# Driver.net
KiCad netlist of a schematic drawn in EAGLE
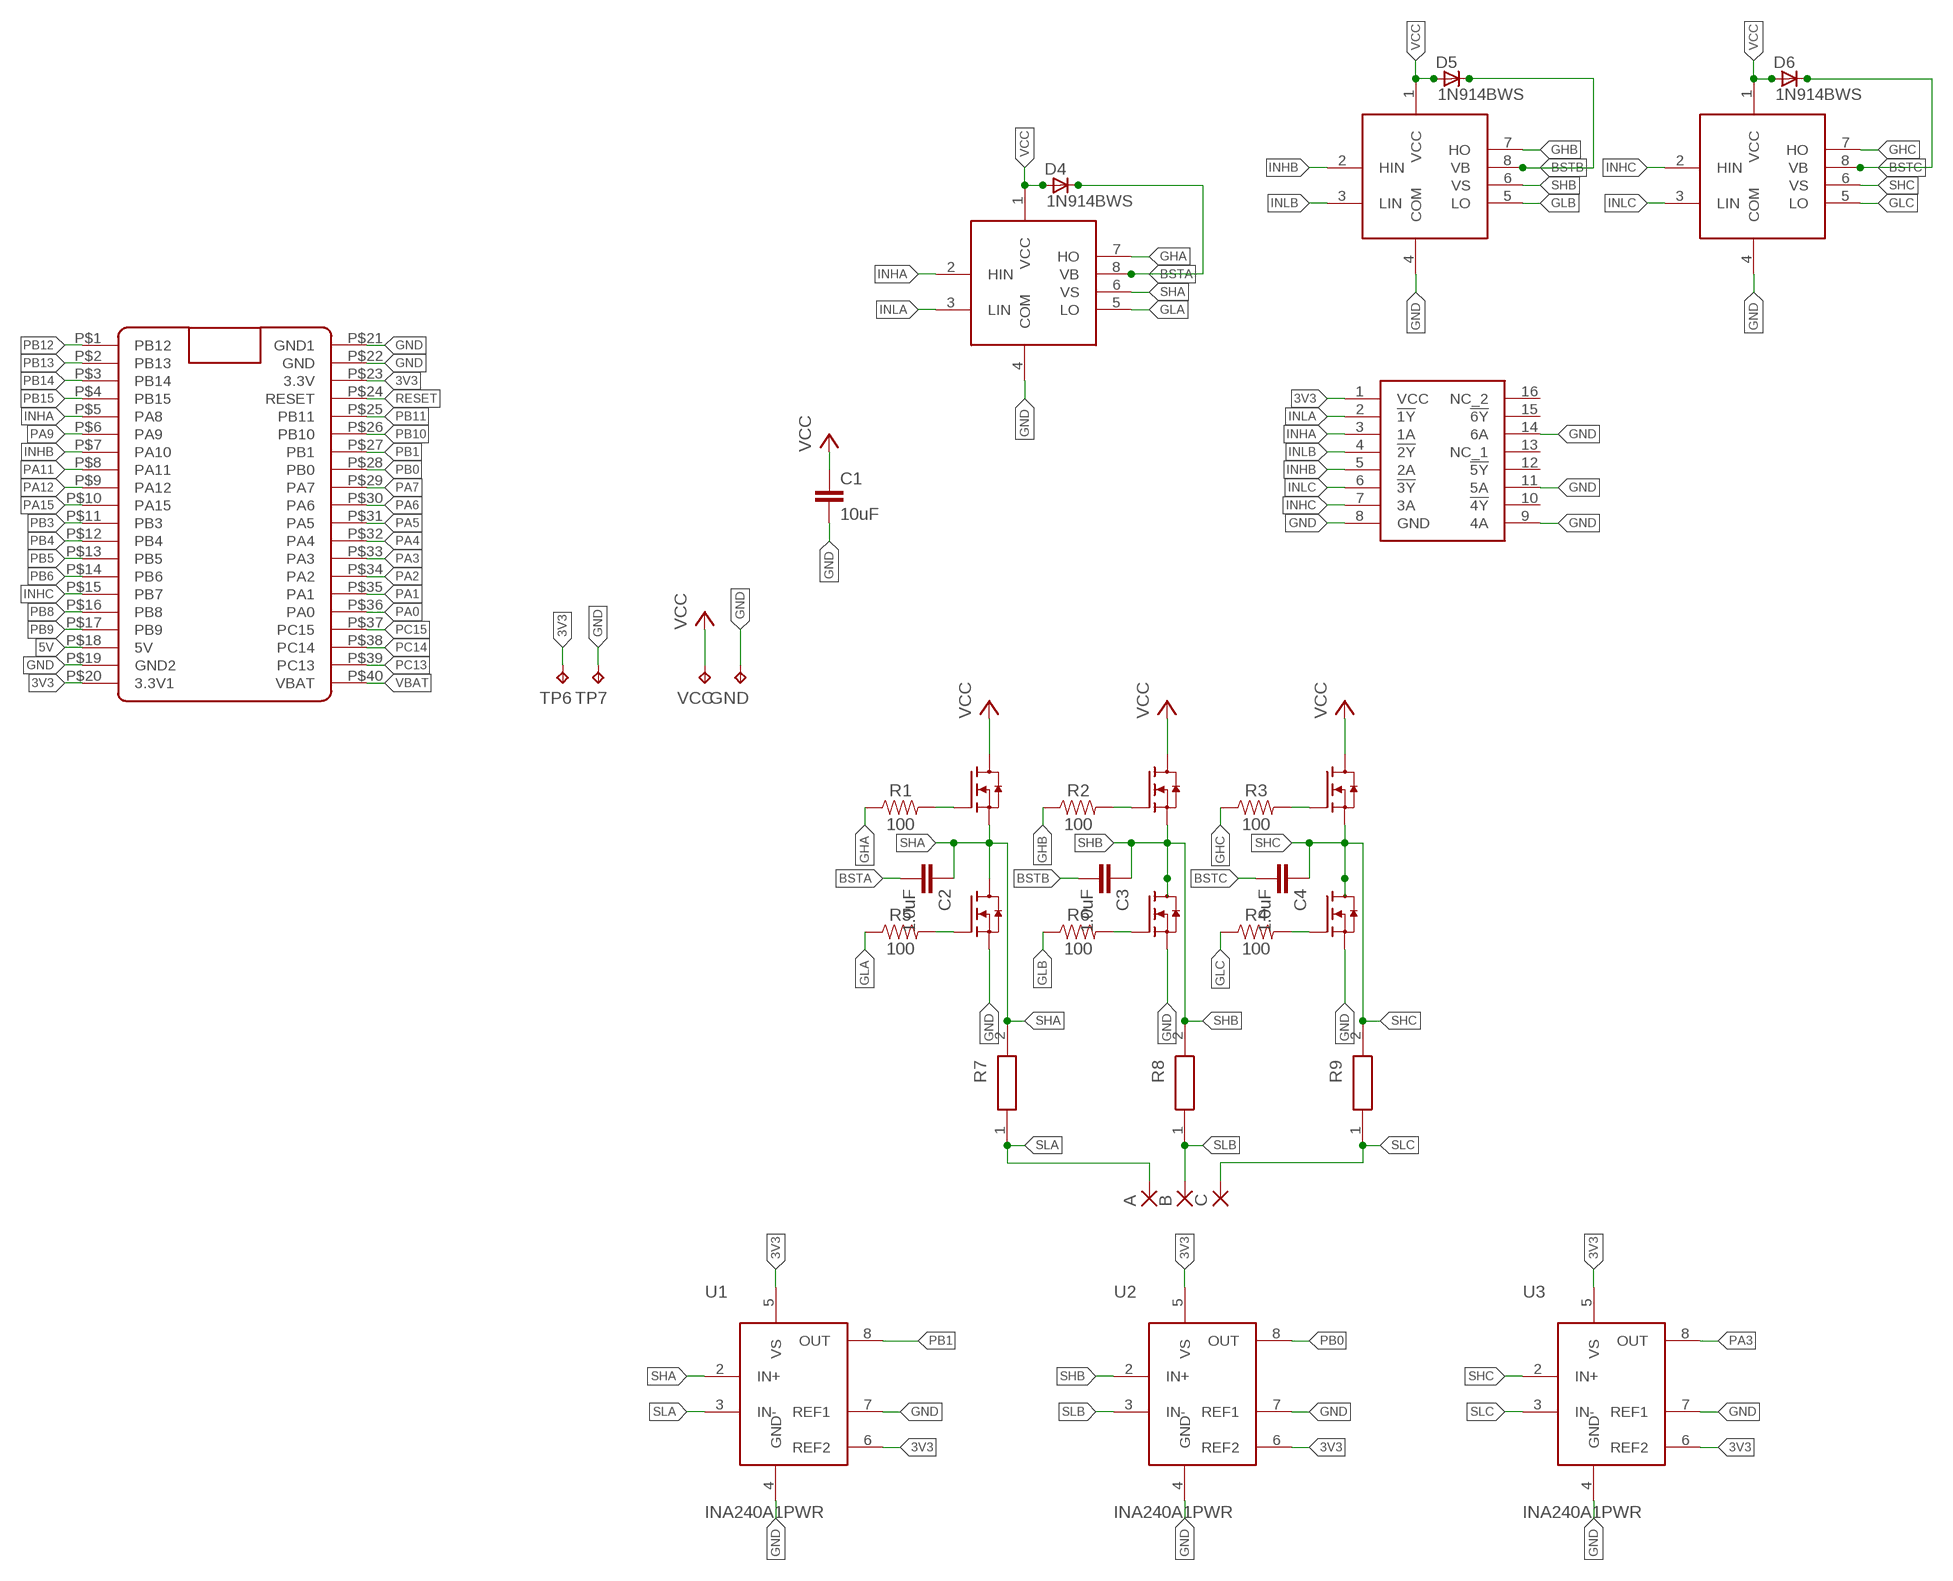
[diagram p0: schematic, sheet 1]

(export (version "E")
  (design (tool "Eeschema 10.0.6"))
  (components
    (comp (ref "A")
      (value "SMD5")
      (footprint "eagle-import:SMD2,54-5,08")
      (libsource (lib "eagle-import") (part "SMD5"))
    )
    (comp (ref "B")
      (value "SMD5")
      (footprint "eagle-import:SMD2,54-5,08")
      (libsource (lib "eagle-import") (part "SMD5"))
    )
    (comp (ref "C")
      (value "SMD5")
      (footprint "eagle-import:SMD2,54-5,08")
      (libsource (lib "eagle-import") (part "SMD5"))
    )
    (comp (ref "C1")
      (value "10uF")
      (footprint "eagle-import:0603")
      (libsource (lib "eagle-import") (part "10UF-0603-6.3V-20%"))
    )
    (comp (ref "C2")
      (value "1.0uF")
      (footprint "eagle-import:0603")
      (libsource (lib "eagle-import") (part "1.0UF-0603-16V-10%"))
    )
    (comp (ref "C3")
      (value "1.0uF")
      (footprint "eagle-import:0603")
      (libsource (lib "eagle-import") (part "1.0UF-0603-16V-10%"))
    )
    (comp (ref "C4")
      (value "1.0uF")
      (footprint "eagle-import:0603")
      (libsource (lib "eagle-import") (part "1.0UF-0603-16V-10%"))
    )
    (comp (ref "D4")
      (value "1N914BWS")
      (footprint "eagle-import:SOD323F")
      (libsource (lib "eagle-import") (part "1N914BWS"))
    )
    (comp (ref "D5")
      (value "1N914BWS")
      (footprint "eagle-import:SOD323F")
      (libsource (lib "eagle-import") (part "1N914BWS"))
    )
    (comp (ref "D6")
      (value "1N914BWS")
      (footprint "eagle-import:SOD323F")
      (libsource (lib "eagle-import") (part "1N914BWS"))
    )
    (comp (ref "GND")
      (value "TPPAD1-13Y")
      (footprint "eagle-import:P1-13Y")
      (libsource (lib "eagle-import") (part "TPPAD1-13Y"))
    )
    (comp (ref "H-A")
      (value "IRLR7843")
      (footprint "eagle-import:TO252")
      (libsource (lib "eagle-import") (part "IRLR7843"))
    )
    (comp (ref "H-B")
      (value "IRLR7843")
      (footprint "eagle-import:TO252")
      (libsource (lib "eagle-import") (part "IRLR7843"))
    )
    (comp (ref "H-C")
      (value "IRLR7843")
      (footprint "eagle-import:TO252")
      (libsource (lib "eagle-import") (part "IRLR7843"))
    )
    (comp (ref "IC2")
      (value "CD74HC4049PWR")
      (footprint "eagle-import:SOP65P640X120-16N")
      (fields (field (name "MOUSER_PART_NUMBER") "595-CD74HC4049PWR"))
      (libsource (lib "eagle-import") (part "CD74HC4049PWR"))
    )
    (comp (ref "L-A")
      (value "IRLR7843")
      (footprint "eagle-import:TO252")
      (libsource (lib "eagle-import") (part "IRLR7843"))
    )
    (comp (ref "L-B")
      (value "IRLR7843")
      (footprint "eagle-import:TO252")
      (libsource (lib "eagle-import") (part "IRLR7843"))
    )
    (comp (ref "L-C")
      (value "IRLR7843")
      (footprint "eagle-import:TO252")
      (libsource (lib "eagle-import") (part "IRLR7843"))
    )
    (comp (ref "R1")
      (value "100")
      (footprint "eagle-import:0603")
      (libsource (lib "eagle-import") (part "100OHM-0603-1/10W-1%"))
    )
    (comp (ref "R2")
      (value "100")
      (footprint "eagle-import:0603")
      (libsource (lib "eagle-import") (part "100OHM-0603-1/10W-1%"))
    )
    (comp (ref "R3")
      (value "100")
      (footprint "eagle-import:0603")
      (libsource (lib "eagle-import") (part "100OHM-0603-1/10W-1%"))
    )
    (comp (ref "R4")
      (value "100")
      (footprint "eagle-import:0603")
      (libsource (lib "eagle-import") (part "100OHM-0603-1/10W-1%"))
    )
    (comp (ref "R5")
      (value "100")
      (footprint "eagle-import:0603")
      (libsource (lib "eagle-import") (part "100OHM-0603-1/10W-1%"))
    )
    (comp (ref "R6")
      (value "100")
      (footprint "eagle-import:0603")
      (libsource (lib "eagle-import") (part "100OHM-0603-1/10W-1%"))
    )
    (comp (ref "R7")
      (value "CR2512-FX-51R1ELF")
      (footprint "eagle-import:RESC6331X75N")
      (fields (field (name "MOUSER_PART_NUMBER") "652-CR2512FX51R1ELF"))
      (libsource (lib "eagle-import") (part "CR2512-FX-51R1ELF"))
    )
    (comp (ref "R8")
      (value "CR2512-FX-51R1ELF")
      (footprint "eagle-import:RESC6331X75N")
      (fields (field (name "MOUSER_PART_NUMBER") "652-CR2512FX51R1ELF"))
      (libsource (lib "eagle-import") (part "CR2512-FX-51R1ELF"))
    )
    (comp (ref "R9")
      (value "CR2512-FX-51R1ELF")
      (footprint "eagle-import:RESC6331X75N")
      (fields (field (name "MOUSER_PART_NUMBER") "652-CR2512FX51R1ELF"))
      (libsource (lib "eagle-import") (part "CR2512-FX-51R1ELF"))
    )
    (comp (ref "TP6")
      (value "TPPAD1-13Y")
      (footprint "eagle-import:P1-13Y")
      (libsource (lib "eagle-import") (part "TPPAD1-13Y"))
    )
    (comp (ref "TP7")
      (value "TPPAD1-13Y")
      (footprint "eagle-import:P1-13Y")
      (libsource (lib "eagle-import") (part "TPPAD1-13Y"))
    )
    (comp (ref "U$1")
      (value "BLUE_PILL")
      (footprint "eagle-import:BLUE_PILL")
      (libsource (lib "eagle-import") (part "BLUE_PILL"))
    )
    (comp (ref "U1")
      (value "INA240A1PWR")
      (footprint "eagle-import:SOP65P640X120-8N")
      (fields (field (name "MF") "Texas Instruments"))
      (libsource (lib "eagle-import") (part "INA240A1PWR"))
    )
    (comp (ref "U2")
      (value "INA240A1PWR")
      (footprint "eagle-import:SOP65P640X120-8N")
      (fields (field (name "MF") "Texas Instruments"))
      (libsource (lib "eagle-import") (part "INA240A1PWR"))
    )
    (comp (ref "U3")
      (value "INA240A1PWR")
      (footprint "eagle-import:SOP65P640X120-8N")
      (fields (field (name "MF") "Texas Instruments"))
      (libsource (lib "eagle-import") (part "INA240A1PWR"))
    )
    (comp (ref "U4")
      (value "SOIC127P610X320-8NSOIC8")
      (footprint "eagle-import:SOIC127P599X175-8N")
      (libsource (lib "eagle-import") (part "SOIC127P610X320-8NSOIC8"))
    )
    (comp (ref "U5")
      (value "SOIC127P610X320-8NSOIC8")
      (footprint "eagle-import:SOIC127P599X175-8N")
      (libsource (lib "eagle-import") (part "SOIC127P610X320-8NSOIC8"))
    )
    (comp (ref "U6")
      (value "SOIC127P610X320-8NSOIC8")
      (footprint "eagle-import:SOIC127P599X175-8N")
      (libsource (lib "eagle-import") (part "SOIC127P610X320-8NSOIC8"))
    )
    (comp (ref "VCC")
      (value "TPPAD1-13Y")
      (footprint "eagle-import:P1-13Y")
      (libsource (lib "eagle-import") (part "TPPAD1-13Y"))
    )
  )
  (nets
    (net (code "1") (name "3V3") (class "Default")
      (node (ref "IC2") (pin "1") (pinfunction "VCC_1") (pintype "bidirectional"))
      (node (ref "TP6") (pin "TP") (pinfunction "TP_TP") (pintype "input"))
      (node (ref "U$1") (pin "P$20") (pinfunction "3.3V1_P$20") (pintype "bidirectional"))
      (node (ref "U$1") (pin "P$23") (pinfunction "3.3V_P$23") (pintype "bidirectional"))
      (node (ref "U1") (pin "5") (pinfunction "VS_5") (pintype "power_in"))
      (node (ref "U1") (pin "6") (pinfunction "REF2_6") (pintype "input"))
      (node (ref "U2") (pin "5") (pinfunction "VS_5") (pintype "power_in"))
      (node (ref "U2") (pin "6") (pinfunction "REF2_6") (pintype "input"))
      (node (ref "U3") (pin "5") (pinfunction "VS_5") (pintype "power_in"))
      (node (ref "U3") (pin "6") (pinfunction "REF2_6") (pintype "input"))
    )
    (net (code "2") (name "5V") (class "Default")
      (node (ref "U$1") (pin "P$18") (pinfunction "5V_P$18") (pintype "bidirectional"))
    )
    (net (code "3") (name "BSTA") (class "Default")
      (node (ref "C2") (pin "2") (pinfunction "2_2") (pintype "passive"))
      (node (ref "D4") (pin "C") (pinfunction "C_C") (pintype "passive"))
      (node (ref "U4") (pin "8") (pinfunction "VB_8") (pintype "bidirectional"))
    )
    (net (code "4") (name "BSTB") (class "Default")
      (node (ref "C3") (pin "2") (pinfunction "2_2") (pintype "passive"))
      (node (ref "D5") (pin "C") (pinfunction "C_C") (pintype "passive"))
      (node (ref "U5") (pin "8") (pinfunction "VB_8") (pintype "bidirectional"))
    )
    (net (code "5") (name "BSTC") (class "Default")
      (node (ref "C4") (pin "2") (pinfunction "2_2") (pintype "passive"))
      (node (ref "D6") (pin "C") (pinfunction "C_C") (pintype "passive"))
      (node (ref "U6") (pin "8") (pinfunction "VB_8") (pintype "bidirectional"))
    )
    (net (code "6") (name "GHA") (class "Default")
      (node (ref "R1") (pin "1") (pinfunction "1_1") (pintype "passive"))
      (node (ref "U4") (pin "7") (pinfunction "HO_7") (pintype "bidirectional"))
    )
    (net (code "7") (name "GHB") (class "Default")
      (node (ref "R2") (pin "1") (pinfunction "1_1") (pintype "passive"))
      (node (ref "U5") (pin "7") (pinfunction "HO_7") (pintype "bidirectional"))
    )
    (net (code "8") (name "GHC") (class "Default")
      (node (ref "R3") (pin "1") (pinfunction "1_1") (pintype "passive"))
      (node (ref "U6") (pin "7") (pinfunction "HO_7") (pintype "bidirectional"))
    )
    (net (code "9") (name "GLA") (class "Default")
      (node (ref "R5") (pin "1") (pinfunction "1_1") (pintype "passive"))
      (node (ref "U4") (pin "5") (pinfunction "LO_5") (pintype "bidirectional"))
    )
    (net (code "10") (name "GLB") (class "Default")
      (node (ref "R6") (pin "1") (pinfunction "1_1") (pintype "passive"))
      (node (ref "U5") (pin "5") (pinfunction "LO_5") (pintype "bidirectional"))
    )
    (net (code "11") (name "GLC") (class "Default")
      (node (ref "R4") (pin "1") (pinfunction "1_1") (pintype "passive"))
      (node (ref "U6") (pin "5") (pinfunction "LO_5") (pintype "bidirectional"))
    )
    (net (code "12") (name "GND") (class "Default")
      (node (ref "C1") (pin "2") (pinfunction "2_2") (pintype "passive"))
      (node (ref "GND") (pin "TP") (pinfunction "TP_TP") (pintype "input"))
      (node (ref "IC2") (pin "11") (pinfunction "5A_11") (pintype "bidirectional"))
      (node (ref "IC2") (pin "14") (pinfunction "6A_14") (pintype "bidirectional"))
      (node (ref "IC2") (pin "8") (pinfunction "GND_8") (pintype "bidirectional"))
      (node (ref "IC2") (pin "9") (pinfunction "4A_9") (pintype "bidirectional"))
      (node (ref "L-A") (pin "2") (pinfunction "S_2") (pintype "passive"))
      (node (ref "L-B") (pin "2") (pinfunction "S_2") (pintype "passive"))
      (node (ref "L-C") (pin "2") (pinfunction "S_2") (pintype "passive"))
      (node (ref "TP7") (pin "TP") (pinfunction "TP_TP") (pintype "input"))
      (node (ref "U$1") (pin "P$19") (pinfunction "GND2_P$19") (pintype "bidirectional"))
      (node (ref "U$1") (pin "P$21") (pinfunction "GND1_P$21") (pintype "power_in"))
      (node (ref "U$1") (pin "P$22") (pinfunction "GND_P$22") (pintype "bidirectional"))
      (node (ref "U1") (pin "4") (pinfunction "GND_4") (pintype "power_in"))
      (node (ref "U1") (pin "7") (pinfunction "REF1_7") (pintype "input"))
      (node (ref "U2") (pin "4") (pinfunction "GND_4") (pintype "power_in"))
      (node (ref "U2") (pin "7") (pinfunction "REF1_7") (pintype "input"))
      (node (ref "U3") (pin "4") (pinfunction "GND_4") (pintype "power_in"))
      (node (ref "U3") (pin "7") (pinfunction "REF1_7") (pintype "input"))
      (node (ref "U4") (pin "4") (pinfunction "COM_4") (pintype "bidirectional"))
      (node (ref "U5") (pin "4") (pinfunction "COM_4") (pintype "bidirectional"))
      (node (ref "U6") (pin "4") (pinfunction "COM_4") (pintype "bidirectional"))
    )
    (net (code "13") (name "INHA") (class "Default")
      (node (ref "IC2") (pin "3") (pinfunction "1A_3") (pintype "bidirectional"))
      (node (ref "U$1") (pin "P$5") (pinfunction "PA8_P$5") (pintype "bidirectional"))
      (node (ref "U4") (pin "2") (pinfunction "HIN_2") (pintype "bidirectional"))
    )
    (net (code "14") (name "INHB") (class "Default")
      (node (ref "IC2") (pin "5") (pinfunction "2A_5") (pintype "bidirectional"))
      (node (ref "U$1") (pin "P$7") (pinfunction "PA10_P$7") (pintype "bidirectional"))
      (node (ref "U5") (pin "2") (pinfunction "HIN_2") (pintype "bidirectional"))
    )
    (net (code "15") (name "INHC") (class "Default")
      (node (ref "IC2") (pin "7") (pinfunction "3A_7") (pintype "bidirectional"))
      (node (ref "U$1") (pin "P$15") (pinfunction "PB7_P$15") (pintype "bidirectional"))
      (node (ref "U6") (pin "2") (pinfunction "HIN_2") (pintype "bidirectional"))
    )
    (net (code "16") (name "INLA") (class "Default")
      (node (ref "IC2") (pin "2") (pinfunction "~{1Y}_2") (pintype "bidirectional"))
      (node (ref "U4") (pin "3") (pinfunction "LIN_3") (pintype "bidirectional"))
    )
    (net (code "17") (name "INLB") (class "Default")
      (node (ref "IC2") (pin "4") (pinfunction "~{2Y}_4") (pintype "bidirectional"))
      (node (ref "U5") (pin "3") (pinfunction "LIN_3") (pintype "bidirectional"))
    )
    (net (code "18") (name "INLC") (class "Default")
      (node (ref "IC2") (pin "6") (pinfunction "~{3Y}_6") (pintype "bidirectional"))
      (node (ref "U6") (pin "3") (pinfunction "LIN_3") (pintype "bidirectional"))
    )
    (net (code "19") (name "Net-(H-A-G)") (class "Default")
      (node (ref "H-A") (pin "1") (pinfunction "G_1") (pintype "passive"))
      (node (ref "R1") (pin "2") (pinfunction "2_2") (pintype "passive"))
    )
    (net (code "20") (name "Net-(H-B-G)") (class "Default")
      (node (ref "H-B") (pin "1") (pinfunction "G_1") (pintype "passive"))
      (node (ref "R2") (pin "2") (pinfunction "2_2") (pintype "passive"))
    )
    (net (code "21") (name "Net-(H-C-G)") (class "Default")
      (node (ref "H-C") (pin "1") (pinfunction "G_1") (pintype "passive"))
      (node (ref "R3") (pin "2") (pinfunction "2_2") (pintype "passive"))
    )
    (net (code "22") (name "Net-(L-A-G)") (class "Default")
      (node (ref "L-A") (pin "1") (pinfunction "G_1") (pintype "passive"))
      (node (ref "R5") (pin "2") (pinfunction "2_2") (pintype "passive"))
    )
    (net (code "23") (name "Net-(L-B-G)") (class "Default")
      (node (ref "L-B") (pin "1") (pinfunction "G_1") (pintype "passive"))
      (node (ref "R6") (pin "2") (pinfunction "2_2") (pintype "passive"))
    )
    (net (code "24") (name "Net-(L-C-G)") (class "Default")
      (node (ref "L-C") (pin "1") (pinfunction "G_1") (pintype "passive"))
      (node (ref "R4") (pin "2") (pinfunction "2_2") (pintype "passive"))
    )
    (net (code "25") (name "PA0") (class "Default")
      (node (ref "U$1") (pin "P$36") (pinfunction "PA0_P$36") (pintype "bidirectional"))
    )
    (net (code "26") (name "PA1") (class "Default")
      (node (ref "U$1") (pin "P$35") (pinfunction "PA1_P$35") (pintype "bidirectional"))
    )
    (net (code "27") (name "PA2") (class "Default")
      (node (ref "U$1") (pin "P$34") (pinfunction "PA2_P$34") (pintype "bidirectional"))
    )
    (net (code "28") (name "PA3") (class "Default")
      (node (ref "U$1") (pin "P$33") (pinfunction "PA3_P$33") (pintype "bidirectional"))
      (node (ref "U3") (pin "8") (pinfunction "OUT_8") (pintype "output"))
    )
    (net (code "29") (name "PA4") (class "Default")
      (node (ref "U$1") (pin "P$32") (pinfunction "PA4_P$32") (pintype "bidirectional"))
    )
    (net (code "30") (name "PA5") (class "Default")
      (node (ref "U$1") (pin "P$31") (pinfunction "PA5_P$31") (pintype "bidirectional"))
    )
    (net (code "31") (name "PA6") (class "Default")
      (node (ref "U$1") (pin "P$30") (pinfunction "PA6_P$30") (pintype "bidirectional"))
    )
    (net (code "32") (name "PA7") (class "Default")
      (node (ref "U$1") (pin "P$29") (pinfunction "PA7_P$29") (pintype "bidirectional"))
    )
    (net (code "33") (name "PA9") (class "Default")
      (node (ref "U$1") (pin "P$6") (pinfunction "PA9_P$6") (pintype "bidirectional"))
    )
    (net (code "34") (name "PA11") (class "Default")
      (node (ref "U$1") (pin "P$8") (pinfunction "PA11_P$8") (pintype "bidirectional"))
    )
    (net (code "35") (name "PA12") (class "Default")
      (node (ref "U$1") (pin "P$9") (pinfunction "PA12_P$9") (pintype "bidirectional"))
    )
    (net (code "36") (name "PA15") (class "Default")
      (node (ref "U$1") (pin "P$10") (pinfunction "PA15_P$10") (pintype "bidirectional"))
    )
    (net (code "37") (name "PB0") (class "Default")
      (node (ref "U$1") (pin "P$28") (pinfunction "PB0_P$28") (pintype "bidirectional"))
      (node (ref "U2") (pin "8") (pinfunction "OUT_8") (pintype "output"))
    )
    (net (code "38") (name "PB1") (class "Default")
      (node (ref "U$1") (pin "P$27") (pinfunction "PB1_P$27") (pintype "bidirectional"))
      (node (ref "U1") (pin "8") (pinfunction "OUT_8") (pintype "output"))
    )
    (net (code "39") (name "PB3") (class "Default")
      (node (ref "U$1") (pin "P$11") (pinfunction "PB3_P$11") (pintype "bidirectional"))
    )
    (net (code "40") (name "PB4") (class "Default")
      (node (ref "U$1") (pin "P$12") (pinfunction "PB4_P$12") (pintype "bidirectional"))
    )
    (net (code "41") (name "PB5") (class "Default")
      (node (ref "U$1") (pin "P$13") (pinfunction "PB5_P$13") (pintype "bidirectional"))
    )
    (net (code "42") (name "PB6") (class "Default")
      (node (ref "U$1") (pin "P$14") (pinfunction "PB6_P$14") (pintype "bidirectional"))
    )
    (net (code "43") (name "PB8") (class "Default")
      (node (ref "U$1") (pin "P$16") (pinfunction "PB8_P$16") (pintype "bidirectional"))
    )
    (net (code "44") (name "PB9") (class "Default")
      (node (ref "U$1") (pin "P$17") (pinfunction "PB9_P$17") (pintype "bidirectional"))
    )
    (net (code "45") (name "PB10") (class "Default")
      (node (ref "U$1") (pin "P$26") (pinfunction "PB10_P$26") (pintype "bidirectional"))
    )
    (net (code "46") (name "PB11") (class "Default")
      (node (ref "U$1") (pin "P$25") (pinfunction "PB11_P$25") (pintype "bidirectional"))
    )
    (net (code "47") (name "PB12") (class "Default")
      (node (ref "U$1") (pin "P$1") (pinfunction "PB12_P$1") (pintype "bidirectional"))
    )
    (net (code "48") (name "PB13") (class "Default")
      (node (ref "U$1") (pin "P$2") (pinfunction "PB13_P$2") (pintype "bidirectional"))
    )
    (net (code "49") (name "PB14") (class "Default")
      (node (ref "U$1") (pin "P$3") (pinfunction "PB14_P$3") (pintype "bidirectional"))
    )
    (net (code "50") (name "PB15") (class "Default")
      (node (ref "U$1") (pin "P$4") (pinfunction "PB15_P$4") (pintype "bidirectional"))
    )
    (net (code "51") (name "PC13") (class "Default")
      (node (ref "U$1") (pin "P$39") (pinfunction "PC13_P$39") (pintype "bidirectional"))
    )
    (net (code "52") (name "PC14") (class "Default")
      (node (ref "U$1") (pin "P$38") (pinfunction "PC14_P$38") (pintype "bidirectional"))
    )
    (net (code "53") (name "PC15") (class "Default")
      (node (ref "U$1") (pin "P$37") (pinfunction "PC15_P$37") (pintype "bidirectional"))
    )
    (net (code "54") (name "RESET") (class "Default")
      (node (ref "U$1") (pin "P$24") (pinfunction "RESET_P$24") (pintype "bidirectional"))
    )
    (net (code "55") (name "SHA") (class "Default")
      (node (ref "C2") (pin "1") (pinfunction "1_1") (pintype "passive"))
      (node (ref "H-A") (pin "2") (pinfunction "S_2") (pintype "passive"))
      (node (ref "L-A") (pin "3") (pinfunction "D_3") (pintype "passive"))
      (node (ref "R7") (pin "2") (pinfunction "2_2") (pintype "bidirectional"))
      (node (ref "U1") (pin "2") (pinfunction "IN+_2") (pintype "input"))
      (node (ref "U4") (pin "6") (pinfunction "VS_6") (pintype "bidirectional"))
    )
    (net (code "56") (name "SHB") (class "Default")
      (node (ref "C3") (pin "1") (pinfunction "1_1") (pintype "passive"))
      (node (ref "H-B") (pin "2") (pinfunction "S_2") (pintype "passive"))
      (node (ref "L-B") (pin "3") (pinfunction "D_3") (pintype "passive"))
      (node (ref "R8") (pin "2") (pinfunction "2_2") (pintype "bidirectional"))
      (node (ref "U2") (pin "2") (pinfunction "IN+_2") (pintype "input"))
      (node (ref "U5") (pin "6") (pinfunction "VS_6") (pintype "bidirectional"))
    )
    (net (code "57") (name "SHC") (class "Default")
      (node (ref "C4") (pin "1") (pinfunction "1_1") (pintype "passive"))
      (node (ref "H-C") (pin "2") (pinfunction "S_2") (pintype "passive"))
      (node (ref "L-C") (pin "3") (pinfunction "D_3") (pintype "passive"))
      (node (ref "R9") (pin "2") (pinfunction "2_2") (pintype "bidirectional"))
      (node (ref "U3") (pin "2") (pinfunction "IN+_2") (pintype "input"))
      (node (ref "U6") (pin "6") (pinfunction "VS_6") (pintype "bidirectional"))
    )
    (net (code "58") (name "SLA") (class "Default")
      (node (ref "A") (pin "1") (pinfunction "P_1") (pintype "passive"))
      (node (ref "R7") (pin "1") (pinfunction "1_1") (pintype "bidirectional"))
      (node (ref "U1") (pin "3") (pinfunction "IN-_3") (pintype "input"))
    )
    (net (code "59") (name "SLB") (class "Default")
      (node (ref "B") (pin "1") (pinfunction "P_1") (pintype "passive"))
      (node (ref "R8") (pin "1") (pinfunction "1_1") (pintype "bidirectional"))
      (node (ref "U2") (pin "3") (pinfunction "IN-_3") (pintype "input"))
    )
    (net (code "60") (name "SLC") (class "Default")
      (node (ref "C") (pin "1") (pinfunction "P_1") (pintype "passive"))
      (node (ref "R9") (pin "1") (pinfunction "1_1") (pintype "bidirectional"))
      (node (ref "U3") (pin "3") (pinfunction "IN-_3") (pintype "input"))
    )
    (net (code "61") (name "VBAT") (class "Default")
      (node (ref "U$1") (pin "P$40") (pinfunction "VBAT_P$40") (pintype "bidirectional"))
    )
    (net (code "62") (name "VCC") (class "Default")
      (node (ref "C1") (pin "1") (pinfunction "1_1") (pintype "passive"))
      (node (ref "D4") (pin "A") (pinfunction "A_A") (pintype "passive"))
      (node (ref "D5") (pin "A") (pinfunction "A_A") (pintype "passive"))
      (node (ref "D6") (pin "A") (pinfunction "A_A") (pintype "passive"))
      (node (ref "H-A") (pin "3") (pinfunction "D_3") (pintype "passive"))
      (node (ref "H-B") (pin "3") (pinfunction "D_3") (pintype "passive"))
      (node (ref "H-C") (pin "3") (pinfunction "D_3") (pintype "passive"))
      (node (ref "U4") (pin "1") (pinfunction "VCC_1") (pintype "bidirectional"))
      (node (ref "U5") (pin "1") (pinfunction "VCC_1") (pintype "bidirectional"))
      (node (ref "U6") (pin "1") (pinfunction "VCC_1") (pintype "bidirectional"))
      (node (ref "VCC") (pin "TP") (pinfunction "TP_TP") (pintype "input"))
    )
    (net (code "63") (name "unconnected-(IC2-NC_1-Pad13)") (class "Default")
      (node (ref "IC2") (pin "13") (pinfunction "NC_1_13") (pintype "bidirectional"))
    )
    (net (code "64") (name "unconnected-(IC2-NC_2-Pad16)") (class "Default")
      (node (ref "IC2") (pin "16") (pinfunction "NC_2_16") (pintype "bidirectional"))
    )
    (net (code "65") (name "unconnected-(IC2-~{4Y}-Pad10)") (class "Default")
      (node (ref "IC2") (pin "10") (pinfunction "~{4Y}_10") (pintype "bidirectional"))
    )
    (net (code "66") (name "unconnected-(IC2-~{5Y}-Pad12)") (class "Default")
      (node (ref "IC2") (pin "12") (pinfunction "~{5Y}_12") (pintype "bidirectional"))
    )
    (net (code "67") (name "unconnected-(IC2-~{6Y}-Pad15)") (class "Default")
      (node (ref "IC2") (pin "15") (pinfunction "~{6Y}_15") (pintype "bidirectional"))
    )
  )
)
